# GPS.net
KiCad netlist of a schematic drawn in Altium Designer
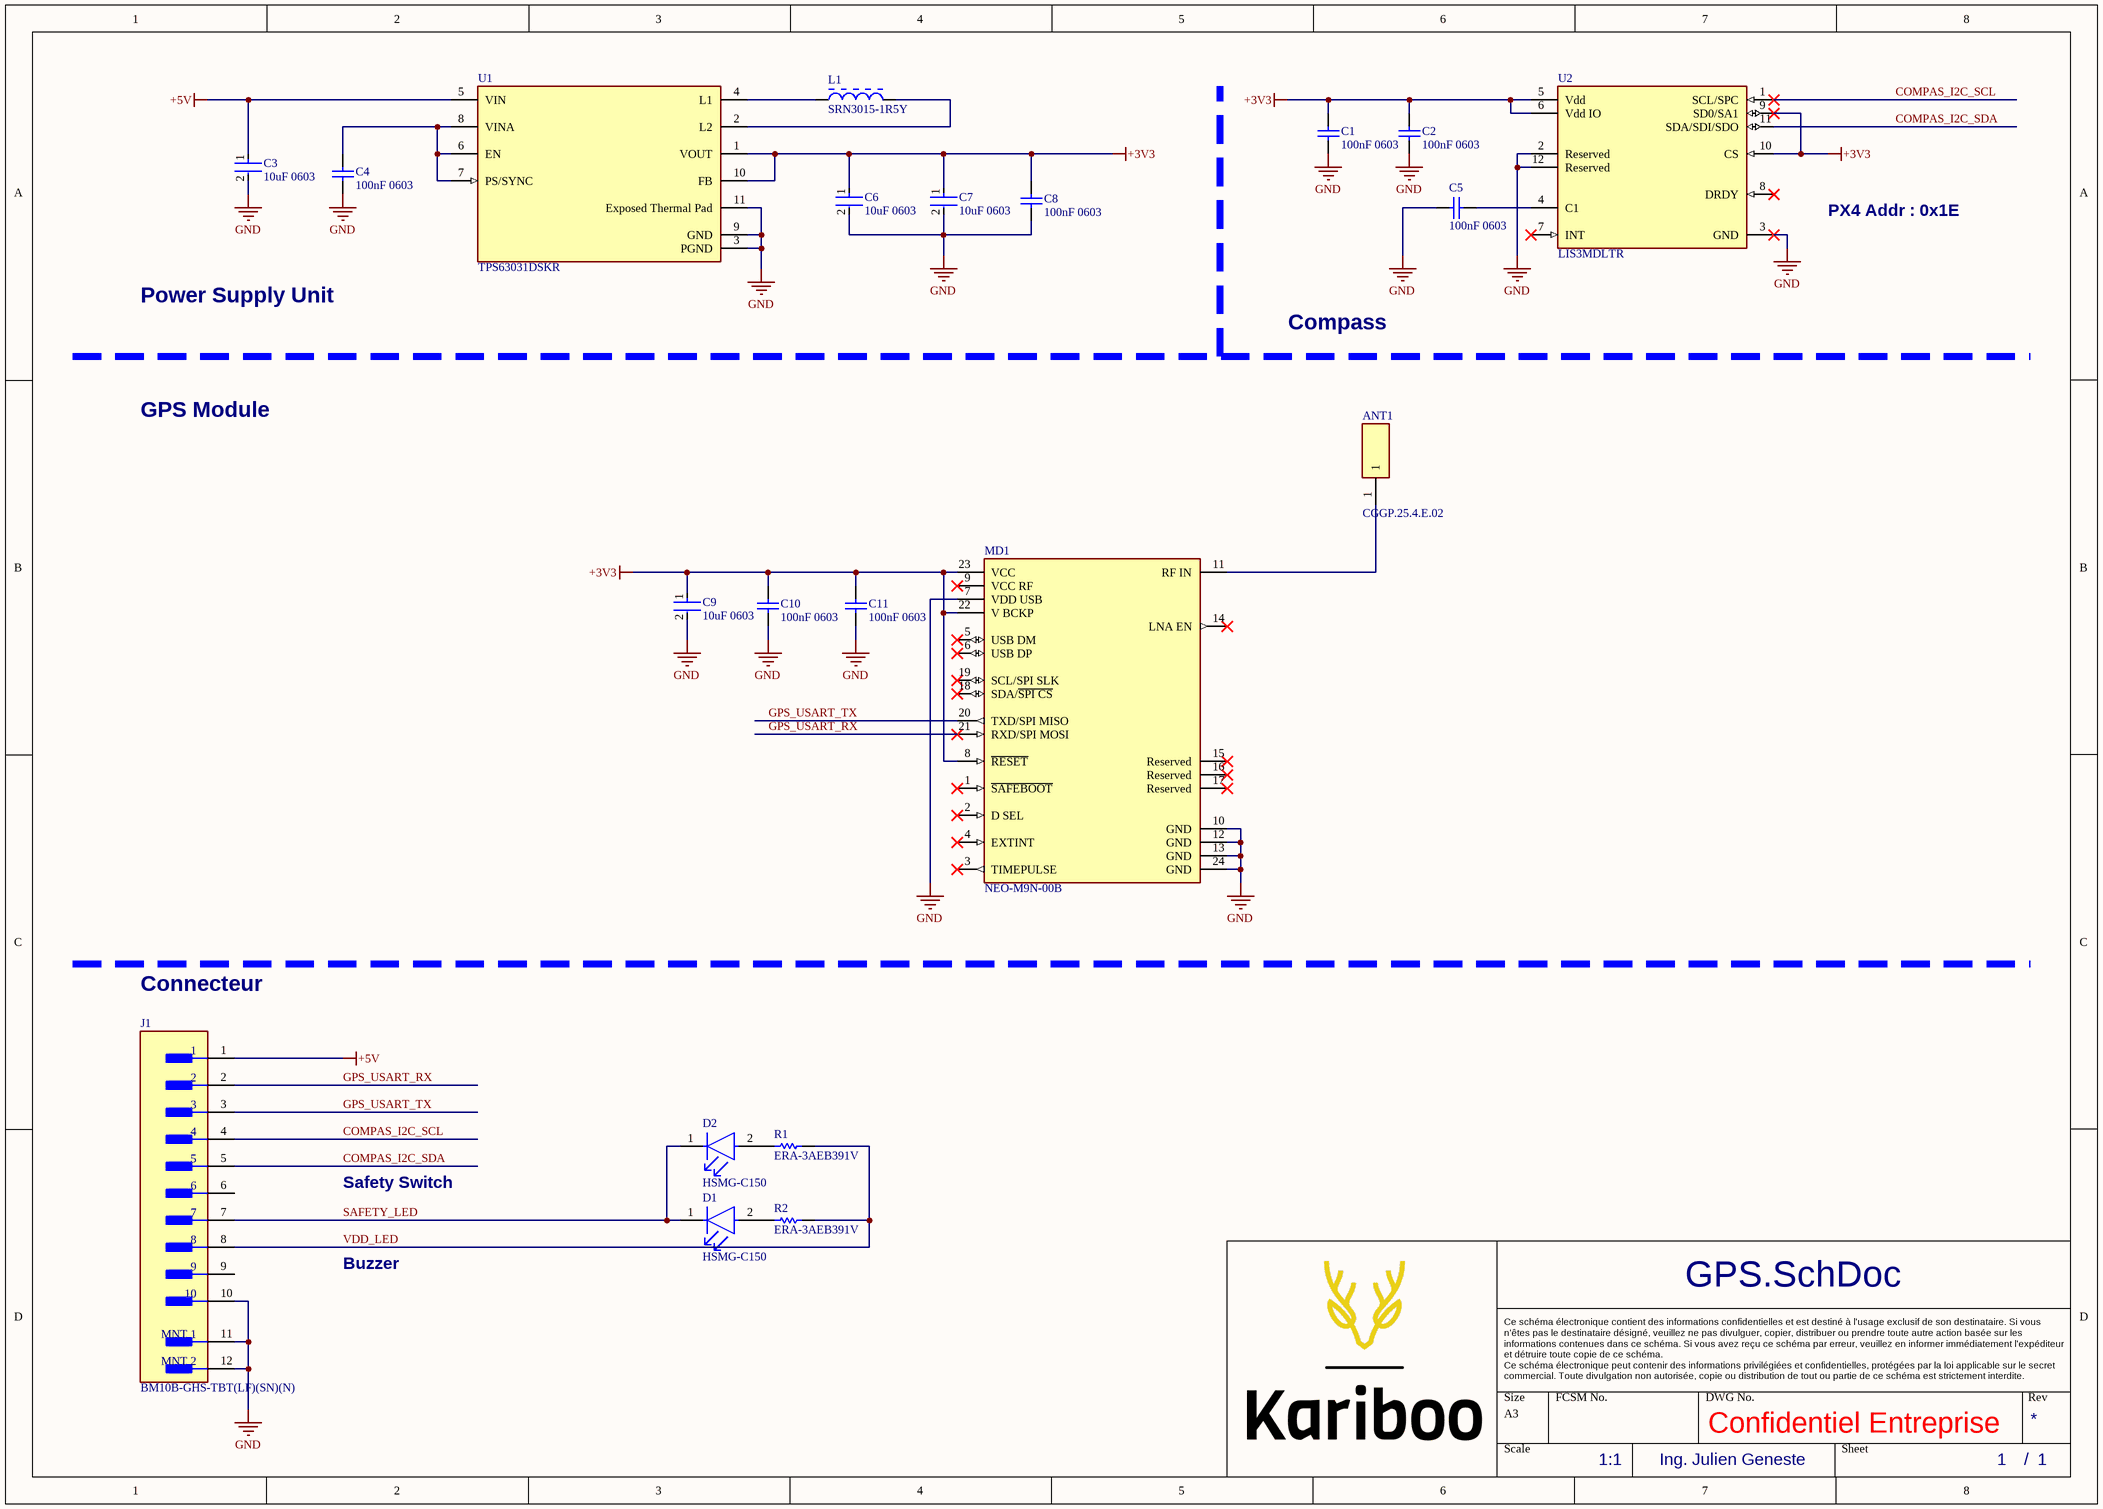
[diagram p0: GPS.SchDoc]

(export (version "E")
  (design (tool "Eeschema 10.0.6"))
  (components
    (comp (ref "ANT1")
      (value "CGGP.25.4.E.02")
      (footprint "SamacSys:CGGP254E02")
      (description "Antenna")
      (fields (field (name "MOUSER PART NUMBER") "960-CGGP.25.4.E.02"))
      (libsource (lib "*") (part "CGGP.25.4.E.02"))
    )
    (comp (ref "C1")
      (value "100nF 0603")
      (footprint "CAPC1608X90X35ML15T15")
      (fields
        (field (name "MANUFACTURER") "AVX Interconnect / Elco")
        (field (name "PART NUMBER") "0603YC104KAZ2A")
      )
      (libsource (lib "Altium Content Vault") (part "CAP"))
    )
    (comp (ref "C2")
      (value "100nF 0603")
      (footprint "CAPC1608X90X35ML15T15")
      (fields
        (field (name "MANUFACTURER") "AVX Interconnect / Elco")
        (field (name "PART NUMBER") "0603YC104KAZ2A")
      )
      (libsource (lib "Altium Content Vault") (part "CAP"))
    )
    (comp (ref "C3")
      (value "10uF 0603")
      (footprint "FP-GRM188-0_1-e0_2_0_55-IPC_A")
      (description "Chip Multilayer Ceramic Capacitors for General Purpose, 0603, 10uF, X5R, 15%, 20%, 6.3V")
      (fields (field (name "VOLTAGE") "6.3V") (field (name "TOLERANCE") "20%"))
      (libsource (lib "Altium Content Vault") (part "02cd4be3c70576c341d710602a673aa"))
    )
    (comp (ref "C4")
      (value "100nF 0603")
      (footprint "CAPC1608X90X35ML15T15")
      (fields
        (field (name "MANUFACTURER") "AVX Interconnect / Elco")
        (field (name "PART NUMBER") "0603YC104KAZ2A")
      )
      (libsource (lib "Altium Content Vault") (part "CAP"))
    )
    (comp (ref "C5")
      (value "100nF 0603")
      (footprint "CAPC1608X90X35ML15T15")
      (fields
        (field (name "MANUFACTURER") "AVX Interconnect / Elco")
        (field (name "PART NUMBER") "0603YC104KAZ2A")
      )
      (libsource (lib "Altium Content Vault") (part "CAP"))
    )
    (comp (ref "C6")
      (value "10uF 0603")
      (footprint "FP-GRM188-0_1-e0_2_0_55-IPC_A")
      (description "Chip Multilayer Ceramic Capacitors for General Purpose, 0603, 10uF, X5R, 15%, 20%, 6.3V")
      (fields (field (name "VOLTAGE") "6.3V") (field (name "TOLERANCE") "20%"))
      (libsource (lib "Altium Content Vault") (part "02cd4be3c70576c341d710602a673aa"))
    )
    (comp (ref "C7")
      (value "10uF 0603")
      (footprint "FP-GRM188-0_1-e0_2_0_55-IPC_A")
      (description "Chip Multilayer Ceramic Capacitors for General Purpose, 0603, 10uF, X5R, 15%, 20%, 6.3V")
      (fields (field (name "VOLTAGE") "6.3V") (field (name "TOLERANCE") "20%"))
      (libsource (lib "Altium Content Vault") (part "02cd4be3c70576c341d710602a673aa"))
    )
    (comp (ref "C8")
      (value "100nF 0603")
      (footprint "CAPC1608X90X35ML15T15")
      (fields
        (field (name "MANUFACTURER") "AVX Interconnect / Elco")
        (field (name "PART NUMBER") "0603YC104KAZ2A")
      )
      (libsource (lib "Altium Content Vault") (part "CAP"))
    )
    (comp (ref "C9")
      (value "10uF 0603")
      (footprint "FP-GRM188-0_1-e0_2_0_55-IPC_A")
      (description "Chip Multilayer Ceramic Capacitors for General Purpose, 0603, 10uF, X5R, 15%, 20%, 6.3V")
      (fields (field (name "VOLTAGE") "6.3V") (field (name "TOLERANCE") "20%"))
      (libsource (lib "Altium Content Vault") (part "02cd4be3c70576c341d710602a673aa"))
    )
    (comp (ref "C10")
      (value "100nF 0603")
      (footprint "CAPC1608X90X35ML15T15")
      (fields
        (field (name "MANUFACTURER") "AVX Interconnect / Elco")
        (field (name "PART NUMBER") "0603YC104KAZ2A")
      )
      (libsource (lib "Altium Content Vault") (part "CAP"))
    )
    (comp (ref "C11")
      (value "100nF 0603")
      (footprint "CAPC1608X90X35ML15T15")
      (fields
        (field (name "MANUFACTURER") "AVX Interconnect / Elco")
        (field (name "PART NUMBER") "0603YC104KAZ2A")
      )
      (libsource (lib "Altium Content Vault") (part "CAP"))
    )
    (comp (ref "D1")
      (value "HSMG-C150")
      (footprint "FP-HSMG-C150-MFG")
      (description "LED GREEN DIFFUSED 1206 SMD")
      (fields
        (field (name "MANUFACTURER") "Broadcom")
        (field (name "OCTOPART") "https://octopart.com/hsmg-c150-broadcom-71131304")
      )
      (libsource (lib "Altium Content Vault") (part "8706943c75ba83719d021d2fdc84c58"))
    )
    (comp (ref "D2")
      (value "HSMG-C150")
      (footprint "FP-HSMG-C150-MFG")
      (description "LED GREEN DIFFUSED 1206 SMD")
      (fields
        (field (name "MANUFACTURER") "Broadcom")
        (field (name "OCTOPART") "https://octopart.com/hsmg-c150-broadcom-71131304")
      )
      (libsource (lib "Altium Content Vault") (part "8706943c75ba83719d021d2fdc84c58"))
    )
    (comp (ref "J1")
      (value "BM10B-GHS-TBT(LF)(SN)(N)")
      (footprint "FP-BM10B-GHS-TBT_LF_SN-MFG")
      (description "CONN HEADER SMD 10POS 1.25MM")
      (libsource (lib "Altium Content Vault") (part "75b8bc8596cc75ee3b2e8049366f7d6"))
    )
    (comp (ref "L1")
      (value "SRN3015-1R5Y")
      (footprint "BOUR-SRN3015-2_V")
      (fields (field (name "MANUFACTURER") "Bourns"))
      (libsource (lib "Altium Content Vault") (part "BOUR-IND-2A"))
    )
    (comp (ref "MD1")
      (value "NEO-M9N-00B")
      (footprint "FP-NEO-M9N-00B-MFG")
      (description "M9 standard precision module")
      (fields
        (field (name "MANUFACTURER") "u-blox")
        (field (name "OCTOPART") "https://octopart.com/neo-m9n-00b-u-blox-107315722")
      )
      (libsource (lib "Altium Content Vault") (part "6afc83350215ab330c065e89349577f"))
    )
    (comp (ref "R1")
      (value "ERA-3AEB391V")
      (footprint "RESC1608X55X30ML20T20")
      (fields (field (name "MANUFACTURER") "Panasonic"))
      (libsource (lib "Altium Content Vault") (part "RES"))
    )
    (comp (ref "R2")
      (value "ERA-3AEB391V")
      (footprint "RESC1608X55X30ML20T20")
      (fields (field (name "MANUFACTURER") "Panasonic"))
      (libsource (lib "Altium Content Vault") (part "RES"))
    )
    (comp (ref "U1")
      (value "TPS63031DSKR")
      (footprint "FP-DSK0010A-MFG")
      (description "IC REG BCK BST ADJ 900MA 10SON")
      (fields
        (field (name "OCTOPART") "https://octopart.com/tps63030dskr-texas+instruments-12188297")
        (field (name "MANUFACTURER") "Texas Instruments")
      )
      (libsource (lib "Altium Content Vault") (part "505b91c7d94d6de1aba830ec9096872"))
    )
    (comp (ref "U2")
      (value "LIS3MDLTR")
      (footprint "FP-VFLGA-12-8365767-MFG")
      (description "SENSOR MR I2C/SPI 12LGA")
      (fields
        (field (name "OCTOPART") "https://octopart.com/lis3mdltr-stmicroelectronics-29403125")
        (field (name "MANUFACTURER") "STMicroelectronics")
      )
      (libsource (lib "Altium Content Vault") (part "41c0331d4207a07573b21020ef49d7d"))
    )
  )
  (nets
    (net (code "1") (name "+3V3") (class "Default")
      (node (ref "C1") (pin "1") (pinfunction "1_1") (pintype "passive"))
      (node (ref "C10") (pin "2") (pinfunction "2_2") (pintype "passive"))
      (node (ref "C11") (pin "2") (pinfunction "2_2") (pintype "passive"))
      (node (ref "C2") (pin "1") (pinfunction "1_1") (pintype "passive"))
      (node (ref "C6") (pin "1") (pinfunction "1_1") (pintype "passive"))
      (node (ref "C7") (pin "1") (pinfunction "1_1") (pintype "passive"))
      (node (ref "C8") (pin "2") (pinfunction "2_2") (pintype "passive"))
      (node (ref "C9") (pin "1") (pinfunction "1_1") (pintype "passive"))
      (node (ref "MD1") (pin "22") (pinfunction "V_BCKP_22") (pintype "power_in"))
      (node (ref "MD1") (pin "23") (pinfunction "VCC_23") (pintype "power_in"))
      (node (ref "MD1") (pin "8") (pinfunction "~{RESET}_8") (pintype "input"))
      (node (ref "U1") (pin "1") (pinfunction "VOUT_1") (pintype "passive"))
      (node (ref "U1") (pin "10") (pinfunction "FB_10") (pintype "passive"))
      (node (ref "U2") (pin "10") (pinfunction "CS_10") (pintype "input"))
      (node (ref "U2") (pin "5") (pinfunction "Vdd_5") (pintype "power_in"))
      (node (ref "U2") (pin "6") (pinfunction "Vdd_IO_6") (pintype "power_in"))
      (node (ref "U2") (pin "9") (pinfunction "SD0/SA1_9") (pintype "bidirectional"))
    )
    (net (code "2") (name "+5V") (class "Default")
      (node (ref "C3") (pin "1") (pinfunction "1_1") (pintype "passive"))
      (node (ref "J1") (pin "1") (pinfunction "1_1") (pintype "passive"))
      (node (ref "U1") (pin "5") (pinfunction "VIN_5") (pintype "power_in"))
    )
    (net (code "3") (name "/COMPAS_I2C_SCL") (class "Default")
      (node (ref "J1") (pin "4") (pinfunction "4_4") (pintype "passive"))
      (node (ref "U2") (pin "1") (pinfunction "SCL/SPC_1") (pintype "input"))
    )
    (net (code "4") (name "/COMPAS_I2C_SDA") (class "Default")
      (node (ref "J1") (pin "5") (pinfunction "5_5") (pintype "passive"))
      (node (ref "U2") (pin "11") (pinfunction "SDA/SDI/SDO_11") (pintype "bidirectional"))
    )
    (net (code "5") (name "/GPS_USART_RX") (class "Default")
      (node (ref "J1") (pin "2") (pinfunction "2_2") (pintype "passive"))
      (node (ref "MD1") (pin "21") (pinfunction "RXD/SPI_MOSI_21") (pintype "input"))
    )
    (net (code "6") (name "/GPS_USART_TX") (class "Default")
      (node (ref "J1") (pin "3") (pinfunction "3_3") (pintype "passive"))
      (node (ref "MD1") (pin "20") (pinfunction "TXD/SPI_MISO_20") (pintype "output"))
    )
    (net (code "7") (name "/SAFETY_LED") (class "Default")
      (node (ref "D1") (pin "1") (pinfunction "C_1") (pintype "passive"))
      (node (ref "D2") (pin "1") (pinfunction "C_1") (pintype "passive"))
      (node (ref "J1") (pin "7") (pinfunction "7_7") (pintype "passive"))
    )
    (net (code "8") (name "/VDD_LED") (class "Default")
      (node (ref "J1") (pin "8") (pinfunction "8_8") (pintype "passive"))
      (node (ref "R1") (pin "2") (pinfunction "2_2") (pintype "passive"))
      (node (ref "R2") (pin "2") (pinfunction "2_2") (pintype "passive"))
    )
    (net (code "9") (name "GND") (class "Default")
      (node (ref "C1") (pin "2") (pinfunction "2_2") (pintype "passive"))
      (node (ref "C10") (pin "1") (pinfunction "1_1") (pintype "passive"))
      (node (ref "C11") (pin "1") (pinfunction "1_1") (pintype "passive"))
      (node (ref "C2") (pin "2") (pinfunction "2_2") (pintype "passive"))
      (node (ref "C3") (pin "2") (pinfunction "2_2") (pintype "passive"))
      (node (ref "C4") (pin "1") (pinfunction "1_1") (pintype "passive"))
      (node (ref "C5") (pin "2") (pinfunction "2_2") (pintype "passive"))
      (node (ref "C6") (pin "2") (pinfunction "2_2") (pintype "passive"))
      (node (ref "C7") (pin "2") (pinfunction "2_2") (pintype "passive"))
      (node (ref "C8") (pin "1") (pinfunction "1_1") (pintype "passive"))
      (node (ref "C9") (pin "2") (pinfunction "2_2") (pintype "passive"))
      (node (ref "J1") (pin "10") (pinfunction "10_10") (pintype "passive"))
      (node (ref "J1") (pin "11") (pinfunction "MNT_1_11") (pintype "passive"))
      (node (ref "J1") (pin "12") (pinfunction "MNT_2_12") (pintype "passive"))
      (node (ref "MD1") (pin "10") (pinfunction "GND_10") (pintype "power_in"))
      (node (ref "MD1") (pin "12") (pinfunction "GND_12") (pintype "power_in"))
      (node (ref "MD1") (pin "13") (pinfunction "GND_13") (pintype "power_in"))
      (node (ref "MD1") (pin "24") (pinfunction "GND_24") (pintype "power_in"))
      (node (ref "MD1") (pin "7") (pinfunction "VDD_USB_7") (pintype "power_in"))
      (node (ref "U1") (pin "11") (pinfunction "Exposed_Thermal_Pad_11") (pintype "power_in"))
      (node (ref "U1") (pin "3") (pinfunction "PGND_3") (pintype "power_in"))
      (node (ref "U1") (pin "9") (pinfunction "GND_9") (pintype "power_in"))
      (node (ref "U2") (pin "12") (pinfunction "Reserved_12") (pintype "passive"))
      (node (ref "U2") (pin "2") (pinfunction "Reserved_2") (pintype "passive"))
      (node (ref "U2") (pin "3") (pinfunction "GND_3") (pintype "power_in"))
    )
    (net (code "10") (name "Net-(D1-A)") (class "Default")
      (node (ref "D1") (pin "2") (pinfunction "A_2") (pintype "passive"))
      (node (ref "R2") (pin "1") (pinfunction "1_1") (pintype "passive"))
    )
    (net (code "11") (name "Net-(D2-A)") (class "Default")
      (node (ref "D2") (pin "2") (pinfunction "A_2") (pintype "passive"))
      (node (ref "R1") (pin "1") (pinfunction "1_1") (pintype "passive"))
    )
    (net (code "12") (name "Net-(MD1-RF_IN)") (class "Default")
      (node (ref "ANT1") (pin "1") (pinfunction "1_1") (pintype "passive"))
      (node (ref "MD1") (pin "11") (pinfunction "RF_IN_11") (pintype "passive"))
    )
    (net (code "13") (name "Net-(U1-EN)") (class "Default")
      (node (ref "C4") (pin "2") (pinfunction "2_2") (pintype "passive"))
      (node (ref "U1") (pin "6") (pinfunction "EN_6") (pintype "passive"))
      (node (ref "U1") (pin "7") (pinfunction "PS/SYNC_7") (pintype "input"))
      (node (ref "U1") (pin "8") (pinfunction "VINA_8") (pintype "power_in"))
    )
    (net (code "14") (name "Net-(U1-L1)") (class "Default")
      (node (ref "L1") (pin "1") (pinfunction "1_1") (pintype "passive"))
      (node (ref "U1") (pin "4") (pinfunction "L1_4") (pintype "passive"))
    )
    (net (code "15") (name "Net-(U1-L2)") (class "Default")
      (node (ref "L1") (pin "2") (pinfunction "2_2") (pintype "passive"))
      (node (ref "U1") (pin "2") (pinfunction "L2_2") (pintype "passive"))
    )
    (net (code "16") (name "Net-(U2-C1)") (class "Default")
      (node (ref "C5") (pin "1") (pinfunction "1_1") (pintype "passive"))
      (node (ref "U2") (pin "4") (pinfunction "C1_4") (pintype "passive"))
    )
    (net (code "17") (name "unconnected-(J1-Pad6)") (class "Default")
      (node (ref "J1") (pin "6") (pinfunction "6_6") (pintype "passive"))
    )
    (net (code "18") (name "unconnected-(J1-Pad9)") (class "Default")
      (node (ref "J1") (pin "9") (pinfunction "9_9") (pintype "passive"))
    )
    (net (code "19") (name "unconnected-(MD1-D_SEL-Pad2)") (class "Default")
      (node (ref "MD1") (pin "2") (pinfunction "D_SEL_2") (pintype "input+no_connect"))
    )
    (net (code "20") (name "unconnected-(MD1-EXTINT-Pad4)") (class "Default")
      (node (ref "MD1") (pin "4") (pinfunction "EXTINT_4") (pintype "input+no_connect"))
    )
    (net (code "21") (name "unconnected-(MD1-LNA_EN-Pad14)") (class "Default")
      (node (ref "MD1") (pin "14") (pinfunction "LNA_EN_14") (pintype "output+no_connect"))
    )
    (net (code "22") (name "unconnected-(MD1-Reserved-Pad15)") (class "Default")
      (node (ref "MD1") (pin "15") (pinfunction "Reserved_15") (pintype "passive+no_connect"))
    )
    (net (code "23") (name "unconnected-(MD1-Reserved-Pad16)") (class "Default")
      (node (ref "MD1") (pin "16") (pinfunction "Reserved_16") (pintype "passive+no_connect"))
    )
    (net (code "24") (name "unconnected-(MD1-Reserved-Pad17)") (class "Default")
      (node (ref "MD1") (pin "17") (pinfunction "Reserved_17") (pintype "passive+no_connect"))
    )
    (net (code "25") (name "unconnected-(MD1-SCL{slash}SPI_SLK-Pad19)") (class "Default")
      (node (ref "MD1") (pin "19") (pinfunction "SCL/SPI_SLK_19") (pintype "bidirectional+no_connect"))
    )
    (net (code "26") (name "unconnected-(MD1-SDA{slash}~{SPI_CS}-Pad18)") (class "Default")
      (node (ref "MD1") (pin "18") (pinfunction "SDA/~{SPI_CS}_18") (pintype "bidirectional+no_connect"))
    )
    (net (code "27") (name "unconnected-(MD1-TIMEPULSE-Pad3)") (class "Default")
      (node (ref "MD1") (pin "3") (pinfunction "TIMEPULSE_3") (pintype "output+no_connect"))
    )
    (net (code "28") (name "unconnected-(MD1-USB_DM-Pad5)") (class "Default")
      (node (ref "MD1") (pin "5") (pinfunction "USB_DM_5") (pintype "bidirectional+no_connect"))
    )
    (net (code "29") (name "unconnected-(MD1-USB_DP-Pad6)") (class "Default")
      (node (ref "MD1") (pin "6") (pinfunction "USB_DP_6") (pintype "bidirectional+no_connect"))
    )
    (net (code "30") (name "unconnected-(MD1-VCC_RF-Pad9)") (class "Default")
      (node (ref "MD1") (pin "9") (pinfunction "VCC_RF_9") (pintype "power_in+no_connect"))
    )
    (net (code "31") (name "unconnected-(MD1-~{SAFEBOOT}-Pad1)") (class "Default")
      (node (ref "MD1") (pin "1") (pinfunction "~{SAFEBOOT}_1") (pintype "input+no_connect"))
    )
    (net (code "32") (name "unconnected-(U2-DRDY-Pad8)") (class "Default")
      (node (ref "U2") (pin "8") (pinfunction "DRDY_8") (pintype "input+no_connect"))
    )
    (net (code "33") (name "unconnected-(U2-INT-Pad7)") (class "Default")
      (node (ref "U2") (pin "7") (pinfunction "INT_7") (pintype "input+no_connect"))
    )
  )
)
